# Row.net
KiCad netlist of a schematic drawn in Altium Designer
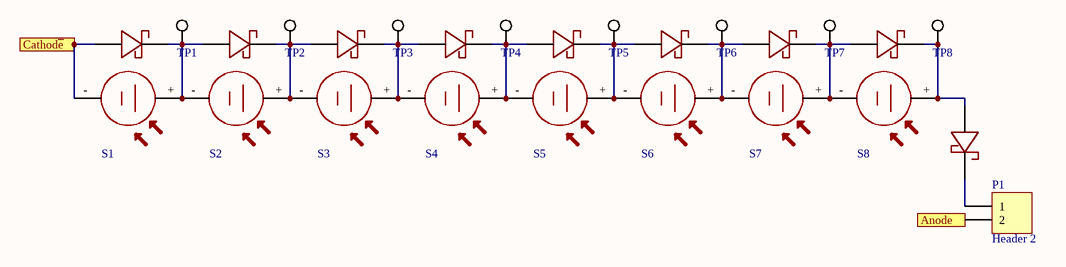
[diagram p0: Row.SchDoc]

(export (version "E")
  (design (tool "Eeschema 10.0.6"))
  (components
    (comp (ref "D1")
      (value "SCHOTTKY_DIODE_B120-FDICT-NDSCHOTTKY_DIODE_B120-FDICT-ND")
      (footprint "SB_DIODE")
      (fields (field (name "LIBRARYNAME") "Solar_Fadi"))
      (libsource (lib "SchLib") (part "SCHOTTKY_DIODE_B120-FDICT-NDSCHOTTKY_DIODE_B120-FDICT-ND"))
    )
    (comp (ref "D2")
      (value "SCHOTTKY_DIODE_B120-FDICT-NDSCHOTTKY_DIODE_B120-FDICT-ND")
      (footprint "SB_DIODE")
      (fields (field (name "LIBRARYNAME") "Solar_Fadi"))
      (libsource (lib "SchLib") (part "SCHOTTKY_DIODE_B120-FDICT-NDSCHOTTKY_DIODE_B120-FDICT-ND"))
    )
    (comp (ref "D3")
      (value "SCHOTTKY_DIODE_B120-FDICT-NDSCHOTTKY_DIODE_B120-FDICT-ND")
      (footprint "SB_DIODE")
      (fields (field (name "LIBRARYNAME") "Solar_Fadi"))
      (libsource (lib "SchLib") (part "SCHOTTKY_DIODE_B120-FDICT-NDSCHOTTKY_DIODE_B120-FDICT-ND"))
    )
    (comp (ref "D4")
      (value "SCHOTTKY_DIODE_B120-FDICT-NDSCHOTTKY_DIODE_B120-FDICT-ND")
      (footprint "SB_DIODE")
      (fields (field (name "LIBRARYNAME") "Solar_Fadi"))
      (libsource (lib "SchLib") (part "SCHOTTKY_DIODE_B120-FDICT-NDSCHOTTKY_DIODE_B120-FDICT-ND"))
    )
    (comp (ref "D5")
      (value "SCHOTTKY_DIODE_B120-FDICT-NDSCHOTTKY_DIODE_B120-FDICT-ND")
      (footprint "SB_DIODE")
      (fields (field (name "LIBRARYNAME") "Solar_Fadi"))
      (libsource (lib "SchLib") (part "SCHOTTKY_DIODE_B120-FDICT-NDSCHOTTKY_DIODE_B120-FDICT-ND"))
    )
    (comp (ref "D6")
      (value "SCHOTTKY_DIODE_B120-FDICT-NDSCHOTTKY_DIODE_B120-FDICT-ND")
      (footprint "SB_DIODE")
      (fields (field (name "LIBRARYNAME") "Solar_Fadi"))
      (libsource (lib "SchLib") (part "SCHOTTKY_DIODE_B120-FDICT-NDSCHOTTKY_DIODE_B120-FDICT-ND"))
    )
    (comp (ref "D7")
      (value "SCHOTTKY_DIODE_B120-FDICT-NDSCHOTTKY_DIODE_B120-FDICT-ND")
      (footprint "SB_DIODE")
      (fields (field (name "LIBRARYNAME") "Solar_Fadi"))
      (libsource (lib "SchLib") (part "SCHOTTKY_DIODE_B120-FDICT-NDSCHOTTKY_DIODE_B120-FDICT-ND"))
    )
    (comp (ref "D8")
      (value "SCHOTTKY_DIODE_B120-FDICT-NDSCHOTTKY_DIODE_B120-FDICT-ND")
      (footprint "SB_DIODE")
      (fields (field (name "LIBRARYNAME") "Solar_Fadi"))
      (libsource (lib "SchLib") (part "SCHOTTKY_DIODE_B120-FDICT-NDSCHOTTKY_DIODE_B120-FDICT-ND"))
    )
    (comp (ref "D9")
      (value "SCHOTTKY_DIODE_B120-FDICT-NDSCHOTTKY_DIODE_B120-FDICT-ND")
      (footprint "SB_DIODE")
      (fields (field (name "LIBRARYNAME") "Solar_Fadi"))
      (libsource (lib "SchLib") (part "SCHOTTKY_DIODE_B120-FDICT-NDSCHOTTKY_DIODE_B120-FDICT-ND"))
    )
    (comp (ref "P1")
      (value "Header 2")
      (footprint "HDR1X2")
      (description "Header, 2-Pin")
      (fields (field (name "PUBLISHER") "Altium Limited"))
      (libsource (lib "Miscellaneous Connectors") (part "Header 2"))
    )
    (comp (ref "S1")
      (value "SOLAR_CELL")
      (footprint "PcbLib1:SOLAR_CELL")
      (libsource (lib "SchLib") (part "SOLAR_CELL"))
    )
    (comp (ref "S2")
      (value "SOLAR_CELL")
      (footprint "PcbLib1:SOLAR_CELL")
      (libsource (lib "SchLib") (part "SOLAR_CELL"))
    )
    (comp (ref "S3")
      (value "SOLAR_CELL")
      (footprint "PcbLib1:SOLAR_CELL")
      (libsource (lib "SchLib") (part "SOLAR_CELL"))
    )
    (comp (ref "S4")
      (value "SOLAR_CELL")
      (footprint "PcbLib1:SOLAR_CELL")
      (libsource (lib "SchLib") (part "SOLAR_CELL"))
    )
    (comp (ref "S5")
      (value "SOLAR_CELL")
      (footprint "PcbLib1:SOLAR_CELL")
      (libsource (lib "SchLib") (part "SOLAR_CELL"))
    )
    (comp (ref "S6")
      (value "SOLAR_CELL")
      (footprint "PcbLib1:SOLAR_CELL")
      (libsource (lib "SchLib") (part "SOLAR_CELL"))
    )
    (comp (ref "S7")
      (value "SOLAR_CELL")
      (footprint "PcbLib1:SOLAR_CELL")
      (libsource (lib "SchLib") (part "SOLAR_CELL"))
    )
    (comp (ref "S8")
      (value "SOLAR_CELL")
      (footprint "PcbLib1:SOLAR_CELL")
      (libsource (lib "SchLib") (part "SOLAR_CELL"))
    )
    (comp (ref "TP1")
      (value "TEST_POINT")
      (footprint "TEST_POINT")
      (libsource (lib "SchLib") (part "TEST_POINT"))
    )
    (comp (ref "TP2")
      (value "TEST_POINT")
      (footprint "TEST_POINT")
      (libsource (lib "SchLib") (part "TEST_POINT"))
    )
    (comp (ref "TP3")
      (value "TEST_POINT")
      (footprint "TEST_POINT")
      (libsource (lib "SchLib") (part "TEST_POINT"))
    )
    (comp (ref "TP4")
      (value "TEST_POINT")
      (footprint "TEST_POINT")
      (libsource (lib "SchLib") (part "TEST_POINT"))
    )
    (comp (ref "TP5")
      (value "TEST_POINT")
      (footprint "TEST_POINT")
      (libsource (lib "SchLib") (part "TEST_POINT"))
    )
    (comp (ref "TP6")
      (value "TEST_POINT")
      (footprint "TEST_POINT")
      (libsource (lib "SchLib") (part "TEST_POINT"))
    )
    (comp (ref "TP7")
      (value "TEST_POINT")
      (footprint "TEST_POINT")
      (libsource (lib "SchLib") (part "TEST_POINT"))
    )
    (comp (ref "TP8")
      (value "TEST_POINT")
      (footprint "TEST_POINT")
      (libsource (lib "SchLib") (part "TEST_POINT"))
    )
  )
  (nets
    (net (code "1") (name "/Anode") (class "Default")
      (node (ref "P1") (pin "2") (pinfunction "2_2") (pintype "passive"))
    )
    (net (code "2") (name "/Cathod~{e}") (class "Default")
      (node (ref "D1") (pin "POS") (pinfunction "POS_POS") (pintype "passive"))
      (node (ref "S1") (pin "-") (pinfunction "-_-") (pintype "passive"))
    )
    (net (code "3") (name "Net-(D1-PadNEG)") (class "Default")
      (node (ref "D1") (pin "NEG") (pinfunction "NEG_NEG") (pintype "passive"))
      (node (ref "D2") (pin "POS") (pinfunction "POS_POS") (pintype "passive"))
      (node (ref "S1") (pin "+") (pinfunction "+_+") (pintype "passive"))
      (node (ref "S2") (pin "-") (pinfunction "-_-") (pintype "passive"))
      (node (ref "TP1") (pin "38") (pinfunction "38_38") (pintype "passive"))
    )
    (net (code "4") (name "Net-(D2-PadNEG)") (class "Default")
      (node (ref "D2") (pin "NEG") (pinfunction "NEG_NEG") (pintype "passive"))
      (node (ref "D3") (pin "POS") (pinfunction "POS_POS") (pintype "passive"))
      (node (ref "S2") (pin "+") (pinfunction "+_+") (pintype "passive"))
      (node (ref "S3") (pin "-") (pinfunction "-_-") (pintype "passive"))
      (node (ref "TP2") (pin "38") (pinfunction "38_38") (pintype "passive"))
    )
    (net (code "5") (name "Net-(D3-PadNEG)") (class "Default")
      (node (ref "D3") (pin "NEG") (pinfunction "NEG_NEG") (pintype "passive"))
      (node (ref "D4") (pin "POS") (pinfunction "POS_POS") (pintype "passive"))
      (node (ref "S3") (pin "+") (pinfunction "+_+") (pintype "passive"))
      (node (ref "S4") (pin "-") (pinfunction "-_-") (pintype "passive"))
      (node (ref "TP3") (pin "38") (pinfunction "38_38") (pintype "passive"))
    )
    (net (code "6") (name "Net-(D4-PadNEG)") (class "Default")
      (node (ref "D4") (pin "NEG") (pinfunction "NEG_NEG") (pintype "passive"))
      (node (ref "D5") (pin "POS") (pinfunction "POS_POS") (pintype "passive"))
      (node (ref "S4") (pin "+") (pinfunction "+_+") (pintype "passive"))
      (node (ref "S5") (pin "-") (pinfunction "-_-") (pintype "passive"))
      (node (ref "TP4") (pin "38") (pinfunction "38_38") (pintype "passive"))
    )
    (net (code "7") (name "Net-(D5-PadNEG)") (class "Default")
      (node (ref "D5") (pin "NEG") (pinfunction "NEG_NEG") (pintype "passive"))
      (node (ref "D6") (pin "POS") (pinfunction "POS_POS") (pintype "passive"))
      (node (ref "S5") (pin "+") (pinfunction "+_+") (pintype "passive"))
      (node (ref "S6") (pin "-") (pinfunction "-_-") (pintype "passive"))
      (node (ref "TP5") (pin "38") (pinfunction "38_38") (pintype "passive"))
    )
    (net (code "8") (name "Net-(D6-PadNEG)") (class "Default")
      (node (ref "D6") (pin "NEG") (pinfunction "NEG_NEG") (pintype "passive"))
      (node (ref "D7") (pin "POS") (pinfunction "POS_POS") (pintype "passive"))
      (node (ref "S6") (pin "+") (pinfunction "+_+") (pintype "passive"))
      (node (ref "S7") (pin "-") (pinfunction "-_-") (pintype "passive"))
      (node (ref "TP6") (pin "38") (pinfunction "38_38") (pintype "passive"))
    )
    (net (code "9") (name "Net-(D7-PadNEG)") (class "Default")
      (node (ref "D7") (pin "NEG") (pinfunction "NEG_NEG") (pintype "passive"))
      (node (ref "D8") (pin "POS") (pinfunction "POS_POS") (pintype "passive"))
      (node (ref "S7") (pin "+") (pinfunction "+_+") (pintype "passive"))
      (node (ref "S8") (pin "-") (pinfunction "-_-") (pintype "passive"))
      (node (ref "TP7") (pin "38") (pinfunction "38_38") (pintype "passive"))
    )
    (net (code "10") (name "Net-(D8-PadNEG)") (class "Default")
      (node (ref "D8") (pin "NEG") (pinfunction "NEG_NEG") (pintype "passive"))
      (node (ref "D9") (pin "POS") (pinfunction "POS_POS") (pintype "passive"))
      (node (ref "S8") (pin "+") (pinfunction "+_+") (pintype "passive"))
      (node (ref "TP8") (pin "38") (pinfunction "38_38") (pintype "passive"))
    )
    (net (code "11") (name "Net-(D9-PadNEG)") (class "Default")
      (node (ref "D9") (pin "NEG") (pinfunction "NEG_NEG") (pintype "passive"))
      (node (ref "P1") (pin "1") (pinfunction "1_1") (pintype "passive"))
    )
  )
)
